# Button_Input_Block.net
KiCad netlist of a schematic drawn in Altium Designer
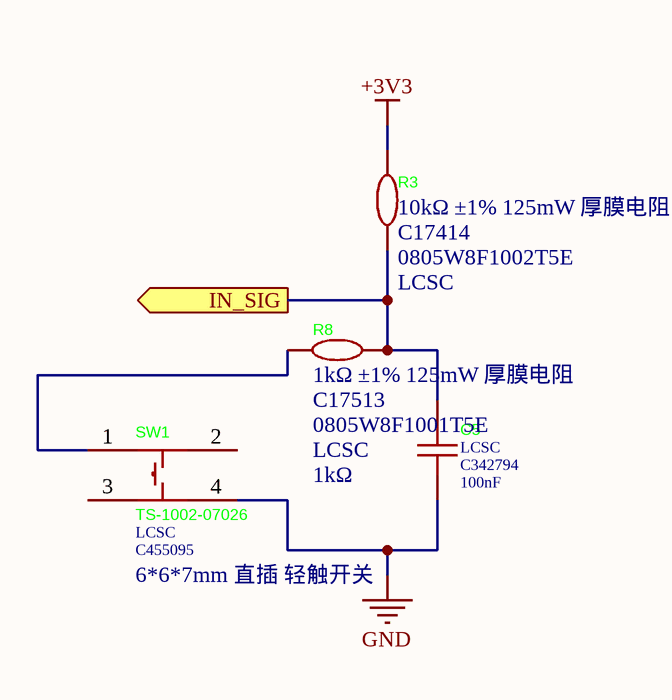
[diagram p0: Button_Input_Block.SchDoc]

(export (version "E")
  (design (tool "Eeschema 10.0.6"))
  (components
    (comp (ref "C5")
      (value "100nF")
      (footprint "CAP-TH_L4.0-W2.5-P5.00-D1.0:CAP-TH_L4.0-W2.5-P5.00-D1.0")
      (fields
        (field (name "MANUFACTURER") "TDK")
        (field (name "MANUFACTURER PART") "FG28X7R1H104KNT06")
        (field (name "TOLERANCE") "±10%")
        (field (name "SUPPLIER") "LCSC")
        (field (name "SUPPLIER PART") "C342794")
      )
      (libsource (lib "FG28X7R1H104KNT061_FG28X7R1H104KNT06") (part "FG28X7R1H104KNT06"))
    )
    (comp (ref "R3")
      (value "10kΩ")
      (footprint "R0805")
      (fields
        (field (name "MANUFACTURER") "UNI-ROYAL(厚声)")
        (field (name "TOLERANCE") "±1%")
        (field (name "LCSC PART NAME") "10kΩ ±1% 125mW 厚膜电阻")
        (field (name "SUPPLIER PART") "C17414")
        (field (name "MANUFACTURER PART") "0805W8F1002T5E")
        (field (name "SUPPLIER") "LCSC")
      )
      (libsource (lib "RES_10k_0805W8F1002T5E1") (part "0805W8F1002T5E"))
    )
    (comp (ref "R8")
      (value "1kΩ")
      (footprint "R0805")
      (fields
        (field (name "MANUFACTURER") "UNI-ROYAL(厚声)")
        (field (name "TOLERANCE") "±1%")
        (field (name "LCSC PART NAME") "1kΩ ±1% 125mW 厚膜电阻")
        (field (name "SUPPLIER PART") "C17513")
        (field (name "MANUFACTURER PART") "0805W8F1001T5E")
        (field (name "SUPPLIER") "LCSC")
      )
      (libsource (lib "1k_0805W8F1001T5E1") (part "0805W8F1001T5E"))
    )
    (comp (ref "SW1")
      (value "TS-1002-07026")
      (footprint "SW-TH_4P-L6.0-W6.0-P4.50-LS6.5:SW-TH_4P-L6.0-W6.0-P4.50-LS6.5")
      (fields
        (field (name "MANUFACTURER") "XUNPU(讯普)")
        (field (name "SUPPLIER") "LCSC")
        (field (name "SUPPLIER PART") "C455095")
        (field (name "LCSC PART NAME") "6*6*7mm 直插 轻触开关")
      )
      (libsource (lib "TS-1002-070261_TS-1002-07026") (part "TS-1002-07026"))
    )
  )
  (nets
    (net (code "1") (name "+3V3") (class "Default")
      (node (ref "R3") (pin "2") (pinfunction "2_2") (pintype "passive"))
    )
    (net (code "2") (name "/IN_SIG") (class "Default")
      (node (ref "C5") (pin "2") (pinfunction "2_2") (pintype "passive"))
      (node (ref "R3") (pin "1") (pinfunction "1_1") (pintype "passive"))
      (node (ref "R8") (pin "2") (pinfunction "2_2") (pintype "passive"))
    )
    (net (code "3") (name "GND") (class "Default")
      (node (ref "C5") (pin "1") (pinfunction "1_1") (pintype "passive"))
      (node (ref "SW1") (pin "4") (pinfunction "4_4") (pintype "passive"))
    )
    (net (code "4") (name "Net-(R8-Pad1)") (class "Default")
      (node (ref "R8") (pin "1") (pinfunction "1_1") (pintype "passive"))
      (node (ref "SW1") (pin "1") (pinfunction "1_1") (pintype "passive"))
    )
    (net (code "5") (name "unconnected-(SW1-Pad2)") (class "Default")
      (node (ref "SW1") (pin "2") (pinfunction "2_2") (pintype "passive"))
    )
    (net (code "6") (name "unconnected-(SW1-Pad3)") (class "Default")
      (node (ref "SW1") (pin "3") (pinfunction "3_3") (pintype "passive"))
    )
  )
)
